# untitled.net
KiCad netlist of a schematic drawn in EAGLE
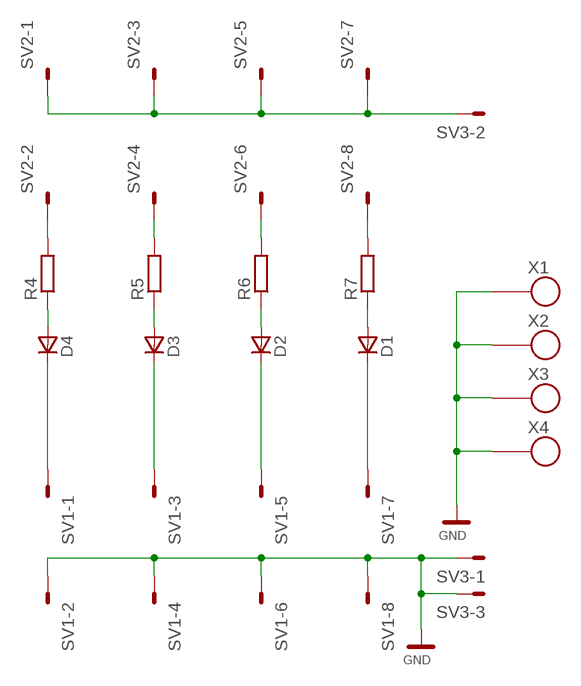
[diagram p0: schematic, sheet 1]

(export (version "E")
  (design (tool "Eeschema 10.0.6"))
  (components
    (comp (ref "D1")
      (value "LED1206")
      (footprint "eagle-import:1206")
      (libsource (lib "eagle-import") (part "LED1206"))
    )
    (comp (ref "D2")
      (value "LED1206")
      (footprint "eagle-import:1206")
      (libsource (lib "eagle-import") (part "LED1206"))
    )
    (comp (ref "D3")
      (value "LED1206")
      (footprint "eagle-import:1206")
      (libsource (lib "eagle-import") (part "LED1206"))
    )
    (comp (ref "D4")
      (value "LED1206")
      (footprint "eagle-import:1206")
      (libsource (lib "eagle-import") (part "LED1206"))
    )
    (comp (ref "R4")
      (value "R0805")
      (footprint "eagle-import:0805")
      (libsource (lib "eagle-import") (part "R0805"))
    )
    (comp (ref "R5")
      (value "R0805")
      (footprint "eagle-import:0805")
      (libsource (lib "eagle-import") (part "R0805"))
    )
    (comp (ref "R6")
      (value "R0805")
      (footprint "eagle-import:0805")
      (libsource (lib "eagle-import") (part "R0805"))
    )
    (comp (ref "R7")
      (value "R0805")
      (footprint "eagle-import:0805")
      (libsource (lib "eagle-import") (part "R0805"))
    )
    (comp (ref "SV1")
      (value "MA04-3")
      (footprint "eagle-import:MA04-2")
      (libsource (lib "eagle-import") (part "MA04-3"))
    )
    (comp (ref "SV2")
      (value "MA04-3")
      (footprint "eagle-import:MA04-2")
      (libsource (lib "eagle-import") (part "MA04-3"))
    )
    (comp (ref "SV3")
      (value "MA03-1")
      (footprint "eagle-import:MA03-1")
      (libsource (lib "eagle-import") (part "MA03-1"))
    )
    (comp (ref "X1")
      (value "SROUB3M")
      (footprint "eagle-import:SROUB3M")
      (libsource (lib "eagle-import") (part "SROUB3M"))
    )
    (comp (ref "X2")
      (value "SROUB3M")
      (footprint "eagle-import:SROUB3M")
      (libsource (lib "eagle-import") (part "SROUB3M"))
    )
    (comp (ref "X3")
      (value "SROUB3M")
      (footprint "eagle-import:SROUB3M")
      (libsource (lib "eagle-import") (part "SROUB3M"))
    )
    (comp (ref "X4")
      (value "SROUB3M")
      (footprint "eagle-import:SROUB3M")
      (libsource (lib "eagle-import") (part "SROUB3M"))
    )
  )
  (nets
    (net (code "1") (name "GND") (class "Default")
      (node (ref "SV1") (pin "2") (pinfunction "P$1_2") (pintype "passive"))
      (node (ref "SV1") (pin "4") (pinfunction "P$1_4") (pintype "passive"))
      (node (ref "SV1") (pin "6") (pinfunction "P$1_6") (pintype "passive"))
      (node (ref "SV1") (pin "8") (pinfunction "P$1_8") (pintype "passive"))
      (node (ref "SV3") (pin "1") (pinfunction "P$1_1") (pintype "passive"))
      (node (ref "SV3") (pin "3") (pinfunction "P$1_3") (pintype "passive"))
      (node (ref "X1") (pin "P$1") (pinfunction "P$1_P$1") (pintype "bidirectional"))
      (node (ref "X2") (pin "P$1") (pinfunction "P$1_P$1") (pintype "bidirectional"))
      (node (ref "X3") (pin "P$1") (pinfunction "P$1_P$1") (pintype "bidirectional"))
      (node (ref "X4") (pin "P$1") (pinfunction "P$1_P$1") (pintype "bidirectional"))
    )
    (net (code "2") (name "Net-(D1-PadA)") (class "Default")
      (node (ref "D1") (pin "A") (pinfunction "A_A") (pintype "passive"))
      (node (ref "R7") (pin "1") (pinfunction "1_1") (pintype "passive"))
    )
    (net (code "3") (name "Net-(D2-PadA)") (class "Default")
      (node (ref "D2") (pin "A") (pinfunction "A_A") (pintype "passive"))
      (node (ref "R6") (pin "1") (pinfunction "1_1") (pintype "passive"))
    )
    (net (code "4") (name "Net-(D3-PadA)") (class "Default")
      (node (ref "D3") (pin "A") (pinfunction "A_A") (pintype "passive"))
      (node (ref "R5") (pin "1") (pinfunction "1_1") (pintype "passive"))
    )
    (net (code "5") (name "Net-(D4-PadA)") (class "Default")
      (node (ref "D4") (pin "A") (pinfunction "A_A") (pintype "passive"))
      (node (ref "R4") (pin "1") (pinfunction "1_1") (pintype "passive"))
    )
    (net (code "6") (name "Net-(SV1A-P$1)") (class "Default")
      (node (ref "D4") (pin "K") (pinfunction "K_K") (pintype "passive"))
      (node (ref "SV1") (pin "1") (pinfunction "P$1_1") (pintype "passive"))
    )
    (net (code "7") (name "Net-(SV1C-P$1)") (class "Default")
      (node (ref "D3") (pin "K") (pinfunction "K_K") (pintype "passive"))
      (node (ref "SV1") (pin "3") (pinfunction "P$1_3") (pintype "passive"))
    )
    (net (code "8") (name "Net-(SV1E-P$1)") (class "Default")
      (node (ref "D2") (pin "K") (pinfunction "K_K") (pintype "passive"))
      (node (ref "SV1") (pin "5") (pinfunction "P$1_5") (pintype "passive"))
    )
    (net (code "9") (name "Net-(SV1G-P$1)") (class "Default")
      (node (ref "D1") (pin "K") (pinfunction "K_K") (pintype "passive"))
      (node (ref "SV1") (pin "7") (pinfunction "P$1_7") (pintype "passive"))
    )
    (net (code "10") (name "Net-(SV2A-P$1)") (class "Default")
      (node (ref "SV2") (pin "1") (pinfunction "P$1_1") (pintype "passive"))
      (node (ref "SV2") (pin "3") (pinfunction "P$1_3") (pintype "passive"))
      (node (ref "SV2") (pin "5") (pinfunction "P$1_5") (pintype "passive"))
      (node (ref "SV2") (pin "7") (pinfunction "P$1_7") (pintype "passive"))
      (node (ref "SV3") (pin "2") (pinfunction "P$1_2") (pintype "passive"))
    )
    (net (code "11") (name "Net-(SV2B-P$1)") (class "Default")
      (node (ref "R4") (pin "2") (pinfunction "2_2") (pintype "passive"))
      (node (ref "SV2") (pin "2") (pinfunction "P$1_2") (pintype "passive"))
    )
    (net (code "12") (name "Net-(SV2D-P$1)") (class "Default")
      (node (ref "R5") (pin "2") (pinfunction "2_2") (pintype "passive"))
      (node (ref "SV2") (pin "4") (pinfunction "P$1_4") (pintype "passive"))
    )
    (net (code "13") (name "Net-(SV2F-P$1)") (class "Default")
      (node (ref "R6") (pin "2") (pinfunction "2_2") (pintype "passive"))
      (node (ref "SV2") (pin "6") (pinfunction "P$1_6") (pintype "passive"))
    )
    (net (code "14") (name "Net-(SV2H-P$1)") (class "Default")
      (node (ref "R7") (pin "2") (pinfunction "2_2") (pintype "passive"))
      (node (ref "SV2") (pin "8") (pinfunction "P$1_8") (pintype "passive"))
    )
  )
)
